# microphone_thingy.net
KiCad netlist of a schematic drawn in Altium Designer
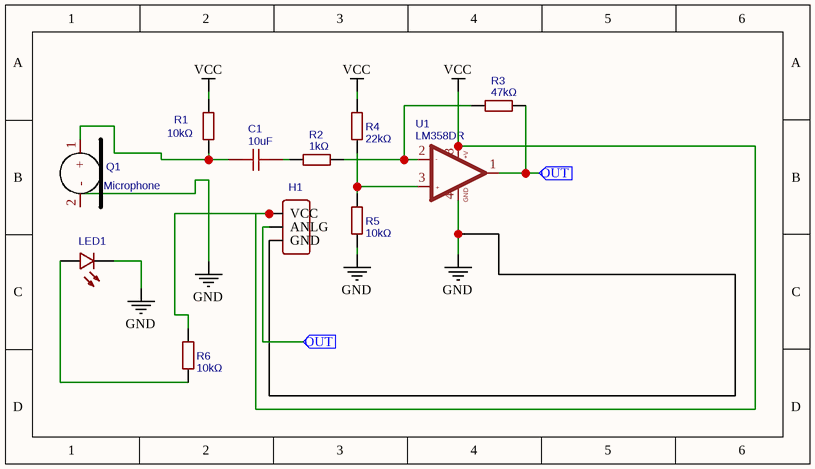
[diagram p0: microphone_thingy.schdoc]

(export (version "E")
  (design (tool "Eeschema 10.0.6"))
  (components
    (comp (ref "C1")
      (value "10uF")
      (fields
        (field (name "MANUFACTURER PART") "CL21A106KAYNNNE")
        (field (name "MANUFACTURER") "SAMSUNG(三星)")
      )
      (libsource (lib "altium-import") (part "root_0_10uF_"))
    )
    (comp (ref "H1")
      (value "Header-Male-2.54_1x3")
      (fields (field (name "MANUFACTURER") "BOOMELE(博穆精密)") (field (name "MANUFACTURER PART") "2.54-1*3P针"))
      (libsource (lib "altium-import") (part "root_0_Header-Male-2.54_1x3_"))
    )
    (comp (ref "LED1")
      (value "19-217/BHC-ZL1M2RY/3T")
      (fields (field (name "MANUFACTURER") "EVERLIGHT(亿光)"))
      (libsource (lib "altium-import") (part "root_2_19-217/BHC-ZL1M2RY/3T_"))
    )
    (comp (ref "Q1")
      (value "Microphone")
      (fields (field (name "CONTRIBUTOR") "Мастерская Ленара"))
      (libsource (lib "altium-import") (part "root_0_Microphone_"))
    )
    (comp (ref "R1")
      (value "10kΩ")
      (fields (field (name "MANUFACTURER") "YAGEO(国巨)") (field (name "MANUFACTURER PART") "RC0402FR-0710KL"))
      (libsource (lib "altium-import") (part "root_1_10kΩ_"))
    )
    (comp (ref "R2")
      (value "1kΩ")
      (fields
        (field (name "MANUFACTURER") "UNI-ROYAL(厚声)")
        (field (name "MANUFACTURER PART") "0402WGF1001TCE")
      )
      (libsource (lib "altium-import") (part "root_0_1kΩ_"))
    )
    (comp (ref "R3")
      (value "47kΩ")
      (fields
        (field (name "MANUFACTURER") "UNI-ROYAL(厚声)")
        (field (name "MANUFACTURER PART") "0402WGF4702TCE")
      )
      (libsource (lib "altium-import") (part "root_0_47kΩ_"))
    )
    (comp (ref "R4")
      (value "22kΩ")
      (fields
        (field (name "MANUFACTURER") "UNI-ROYAL(厚声)")
        (field (name "MANUFACTURER PART") "0402WGF2202TCE")
      )
      (libsource (lib "altium-import") (part "root_1_22kΩ_"))
    )
    (comp (ref "R5")
      (value "10kΩ")
      (fields (field (name "MANUFACTURER") "YAGEO(国巨)") (field (name "MANUFACTURER PART") "RC0402FR-0710KL"))
      (libsource (lib "altium-import") (part "root_1_10kΩ_"))
    )
    (comp (ref "R6")
      (value "10kΩ")
      (fields (field (name "MANUFACTURER") "YAGEO(国巨)") (field (name "MANUFACTURER PART") "RC0402FR-0710KL"))
      (libsource (lib "altium-import") (part "root_1_10kΩ_"))
    )
    (comp (ref "U1")
      (value "LM358DR")
      (fields (field (name "SUBPART_NO") "1") (field (name "MANUFACTURER") "TI(德州仪器)"))
      (libsource (lib "altium-import") (part "root_0_LM358DR_"))
    )
  )
  (nets
    (net (code "1") (name "/OUT") (class "Default")
      (node (ref "H1") (pin "2") (pinfunction "ANLG_2") (pintype "passive"))
      (node (ref "R3") (pin "2") (pinfunction "2_2") (pintype "passive"))
      (node (ref "U1") (pin "1") (pinfunction "OUT1_1") (pintype "passive"))
    )
    (net (code "2") (name "GND") (class "Default")
      (node (ref "H1") (pin "3") (pinfunction "GND_3") (pintype "passive"))
      (node (ref "LED1") (pin "1") (pinfunction "C_1") (pintype "passive"))
      (node (ref "Q1") (pin "2") (pinfunction "-_2") (pintype "passive"))
      (node (ref "R5") (pin "1") (pinfunction "1_1") (pintype "passive"))
      (node (ref "U1") (pin "4") (pinfunction "GND_4") (pintype "passive"))
    )
    (net (code "3") (name "Net-(C1-Pad2)") (class "Default")
      (node (ref "C1") (pin "2") (pinfunction "2_2") (pintype "passive"))
      (node (ref "R2") (pin "1") (pinfunction "1_1") (pintype "passive"))
    )
    (net (code "4") (name "Net-(LED1-A)") (class "Default")
      (node (ref "LED1") (pin "2") (pinfunction "A_2") (pintype "passive"))
      (node (ref "R6") (pin "1") (pinfunction "1_1") (pintype "passive"))
    )
    (net (code "5") (name "Net-(Q1-+)") (class "Default")
      (node (ref "C1") (pin "1") (pinfunction "1_1") (pintype "passive"))
      (node (ref "Q1") (pin "1") (pinfunction "+_1") (pintype "passive"))
      (node (ref "R1") (pin "1") (pinfunction "1_1") (pintype "passive"))
    )
    (net (code "6") (name "Net-(U1-+IN1)") (class "Default")
      (node (ref "R4") (pin "1") (pinfunction "1_1") (pintype "passive"))
      (node (ref "R5") (pin "2") (pinfunction "2_2") (pintype "passive"))
      (node (ref "U1") (pin "3") (pinfunction "+IN1_3") (pintype "passive"))
    )
    (net (code "7") (name "Net-(U1--IN1)") (class "Default")
      (node (ref "R2") (pin "2") (pinfunction "2_2") (pintype "passive"))
      (node (ref "R3") (pin "1") (pinfunction "1_1") (pintype "passive"))
      (node (ref "U1") (pin "2") (pinfunction "-IN1_2") (pintype "passive"))
    )
    (net (code "8") (name "VCC") (class "Default")
      (node (ref "H1") (pin "1") (pinfunction "VCC_1") (pintype "passive"))
      (node (ref "R1") (pin "2") (pinfunction "2_2") (pintype "passive"))
      (node (ref "R4") (pin "2") (pinfunction "2_2") (pintype "passive"))
      (node (ref "R6") (pin "2") (pinfunction "2_2") (pintype "passive"))
      (node (ref "U1") (pin "8") (pinfunction "+V_8") (pintype "passive"))
    )
  )
)
